# 1LED.net
KiCad netlist of a schematic drawn in EAGLE
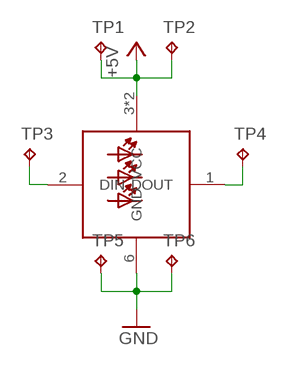
[diagram p0: schematic, sheet 1]

(export (version "E")
  (design (tool "Eeschema 10.0.6"))
  (components
    (comp (ref "TP1")
      (value "TPTP15SQ")
      (footprint "eagle-import:TP15SQ")
      (libsource (lib "eagle-import") (part "TPTP15SQ"))
    )
    (comp (ref "TP2")
      (value "TPTP15SQ")
      (footprint "eagle-import:TP15SQ")
      (libsource (lib "eagle-import") (part "TPTP15SQ"))
    )
    (comp (ref "TP3")
      (value "TPTP15SQ")
      (footprint "eagle-import:TP15SQ")
      (libsource (lib "eagle-import") (part "TPTP15SQ"))
    )
    (comp (ref "TP4")
      (value "TPTP15SQ")
      (footprint "eagle-import:TP15SQ")
      (libsource (lib "eagle-import") (part "TPTP15SQ"))
    )
    (comp (ref "TP5")
      (value "TPTP15SQ")
      (footprint "eagle-import:TP15SQ")
      (libsource (lib "eagle-import") (part "TPTP15SQ"))
    )
    (comp (ref "TP6")
      (value "TPTP15SQ")
      (footprint "eagle-import:TP15SQ")
      (libsource (lib "eagle-import") (part "TPTP15SQ"))
    )
    (comp (ref "U$1")
      (value "RGBLED")
      (footprint "eagle-import:RGBLED")
      (libsource (lib "eagle-import") (part "RGBLED"))
    )
  )
  (nets
    (net (code "1") (name "+5V") (class "Default")
      (node (ref "TP1") (pin "TP") (pinfunction "TP_TP") (pintype "input"))
      (node (ref "TP2") (pin "TP") (pinfunction "TP_TP") (pintype "input"))
      (node (ref "U$1") (pin "3") (pinfunction "VCC_3") (pintype "bidirectional"))
      (node (ref "U$1") (pin "5") (pinfunction "VCC_5") (pintype "bidirectional"))
    )
    (net (code "2") (name "GND") (class "Default")
      (node (ref "TP5") (pin "TP") (pinfunction "TP_TP") (pintype "input"))
      (node (ref "TP6") (pin "TP") (pinfunction "TP_TP") (pintype "input"))
      (node (ref "U$1") (pin "6") (pinfunction "GND_6") (pintype "bidirectional"))
    )
    (net (code "3") (name "Net-(U$1-DIN)") (class "Default")
      (node (ref "TP3") (pin "TP") (pinfunction "TP_TP") (pintype "input"))
      (node (ref "U$1") (pin "2") (pinfunction "DIN_2") (pintype "bidirectional"))
    )
    (net (code "4") (name "Net-(U$1-DOUT)") (class "Default")
      (node (ref "TP4") (pin "TP") (pinfunction "TP_TP") (pintype "input"))
      (node (ref "U$1") (pin "1") (pinfunction "DOUT_1") (pintype "bidirectional"))
    )
  )
)
